# Sheet1_PCI_mez_to_MB.net
KiCad netlist of a schematic drawn in Altium Designer
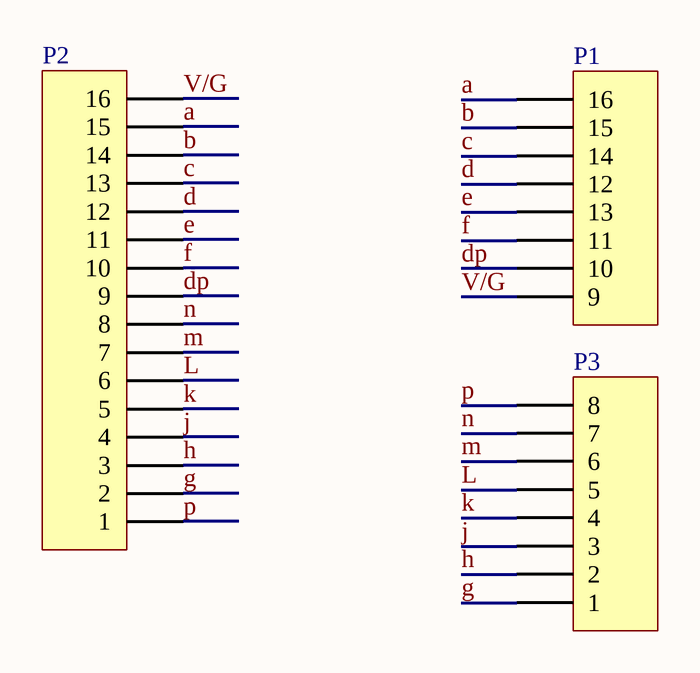
[diagram p0: Sheet1_PCI_mez_to_MB.SchDoc]

(export (version "E")
  (design (tool "Eeschema 10.0.6"))
  (components
    (comp (ref "P1")
      (value "Header 8")
      (footprint "HDR1X8")
      (description "Header, 8-Pin")
      (fields (field (name "PUBLISHER") "Altium Limited"))
      (libsource (lib "Miscellaneous Connectors") (part "Header 8"))
    )
    (comp (ref "P2")
      (value "Header 16")
      (footprint "HDR1X16")
      (description "Header, 16-Pin")
      (fields (field (name "PUBLISHER") "Altium Limited"))
      (libsource (lib "Miscellaneous Connectors") (part "Header 16"))
    )
    (comp (ref "P3")
      (value "Header 8")
      (footprint "HDR1X8")
      (description "Header, 8-Pin")
      (fields (field (name "PUBLISHER") "Altium Limited"))
      (libsource (lib "") (part "Header 8_1"))
    )
  )
  (nets
    (net (code "1") (name "/L") (class "Default")
      (node (ref "P2") (pin "6") (pinfunction "6_6") (pintype "passive"))
      (node (ref "P3") (pin "5") (pinfunction "5_5") (pintype "passive"))
    )
    (net (code "2") (name "/V{slash}G") (class "Default")
      (node (ref "P1") (pin "8") (pinfunction "9_8") (pintype "passive"))
      (node (ref "P2") (pin "16") (pinfunction "16_16") (pintype "passive"))
    )
    (net (code "3") (name "/a") (class "Default")
      (node (ref "P1") (pin "1") (pinfunction "16_1") (pintype "passive"))
      (node (ref "P2") (pin "15") (pinfunction "15_15") (pintype "passive"))
    )
    (net (code "4") (name "/b") (class "Default")
      (node (ref "P1") (pin "2") (pinfunction "15_2") (pintype "passive"))
      (node (ref "P2") (pin "14") (pinfunction "14_14") (pintype "passive"))
    )
    (net (code "5") (name "/c") (class "Default")
      (node (ref "P1") (pin "3") (pinfunction "14_3") (pintype "passive"))
      (node (ref "P2") (pin "13") (pinfunction "13_13") (pintype "passive"))
    )
    (net (code "6") (name "/d") (class "Default")
      (node (ref "P1") (pin "4") (pinfunction "12_4") (pintype "passive"))
      (node (ref "P2") (pin "12") (pinfunction "12_12") (pintype "passive"))
    )
    (net (code "7") (name "/dp") (class "Default")
      (node (ref "P1") (pin "7") (pinfunction "10_7") (pintype "passive"))
      (node (ref "P2") (pin "9") (pinfunction "9_9") (pintype "passive"))
    )
    (net (code "8") (name "/e") (class "Default")
      (node (ref "P1") (pin "5") (pinfunction "13_5") (pintype "passive"))
      (node (ref "P2") (pin "11") (pinfunction "11_11") (pintype "passive"))
    )
    (net (code "9") (name "/f") (class "Default")
      (node (ref "P1") (pin "6") (pinfunction "11_6") (pintype "passive"))
      (node (ref "P2") (pin "10") (pinfunction "10_10") (pintype "passive"))
    )
    (net (code "10") (name "/g") (class "Default")
      (node (ref "P2") (pin "2") (pinfunction "2_2") (pintype "passive"))
      (node (ref "P3") (pin "1") (pinfunction "1_1") (pintype "passive"))
    )
    (net (code "11") (name "/h") (class "Default")
      (node (ref "P2") (pin "3") (pinfunction "3_3") (pintype "passive"))
      (node (ref "P3") (pin "2") (pinfunction "2_2") (pintype "passive"))
    )
    (net (code "12") (name "/j") (class "Default")
      (node (ref "P2") (pin "4") (pinfunction "4_4") (pintype "passive"))
      (node (ref "P3") (pin "3") (pinfunction "3_3") (pintype "passive"))
    )
    (net (code "13") (name "/k") (class "Default")
      (node (ref "P2") (pin "5") (pinfunction "5_5") (pintype "passive"))
      (node (ref "P3") (pin "4") (pinfunction "4_4") (pintype "passive"))
    )
    (net (code "14") (name "/m") (class "Default")
      (node (ref "P2") (pin "7") (pinfunction "7_7") (pintype "passive"))
      (node (ref "P3") (pin "6") (pinfunction "6_6") (pintype "passive"))
    )
    (net (code "15") (name "/n") (class "Default")
      (node (ref "P2") (pin "8") (pinfunction "8_8") (pintype "passive"))
      (node (ref "P3") (pin "7") (pinfunction "7_7") (pintype "passive"))
    )
    (net (code "16") (name "/p") (class "Default")
      (node (ref "P2") (pin "1") (pinfunction "1_1") (pintype "passive"))
      (node (ref "P3") (pin "8") (pinfunction "8_8") (pintype "passive"))
    )
  )
)
